# PowerSupply.net
KiCad netlist of a schematic drawn in Altium Designer
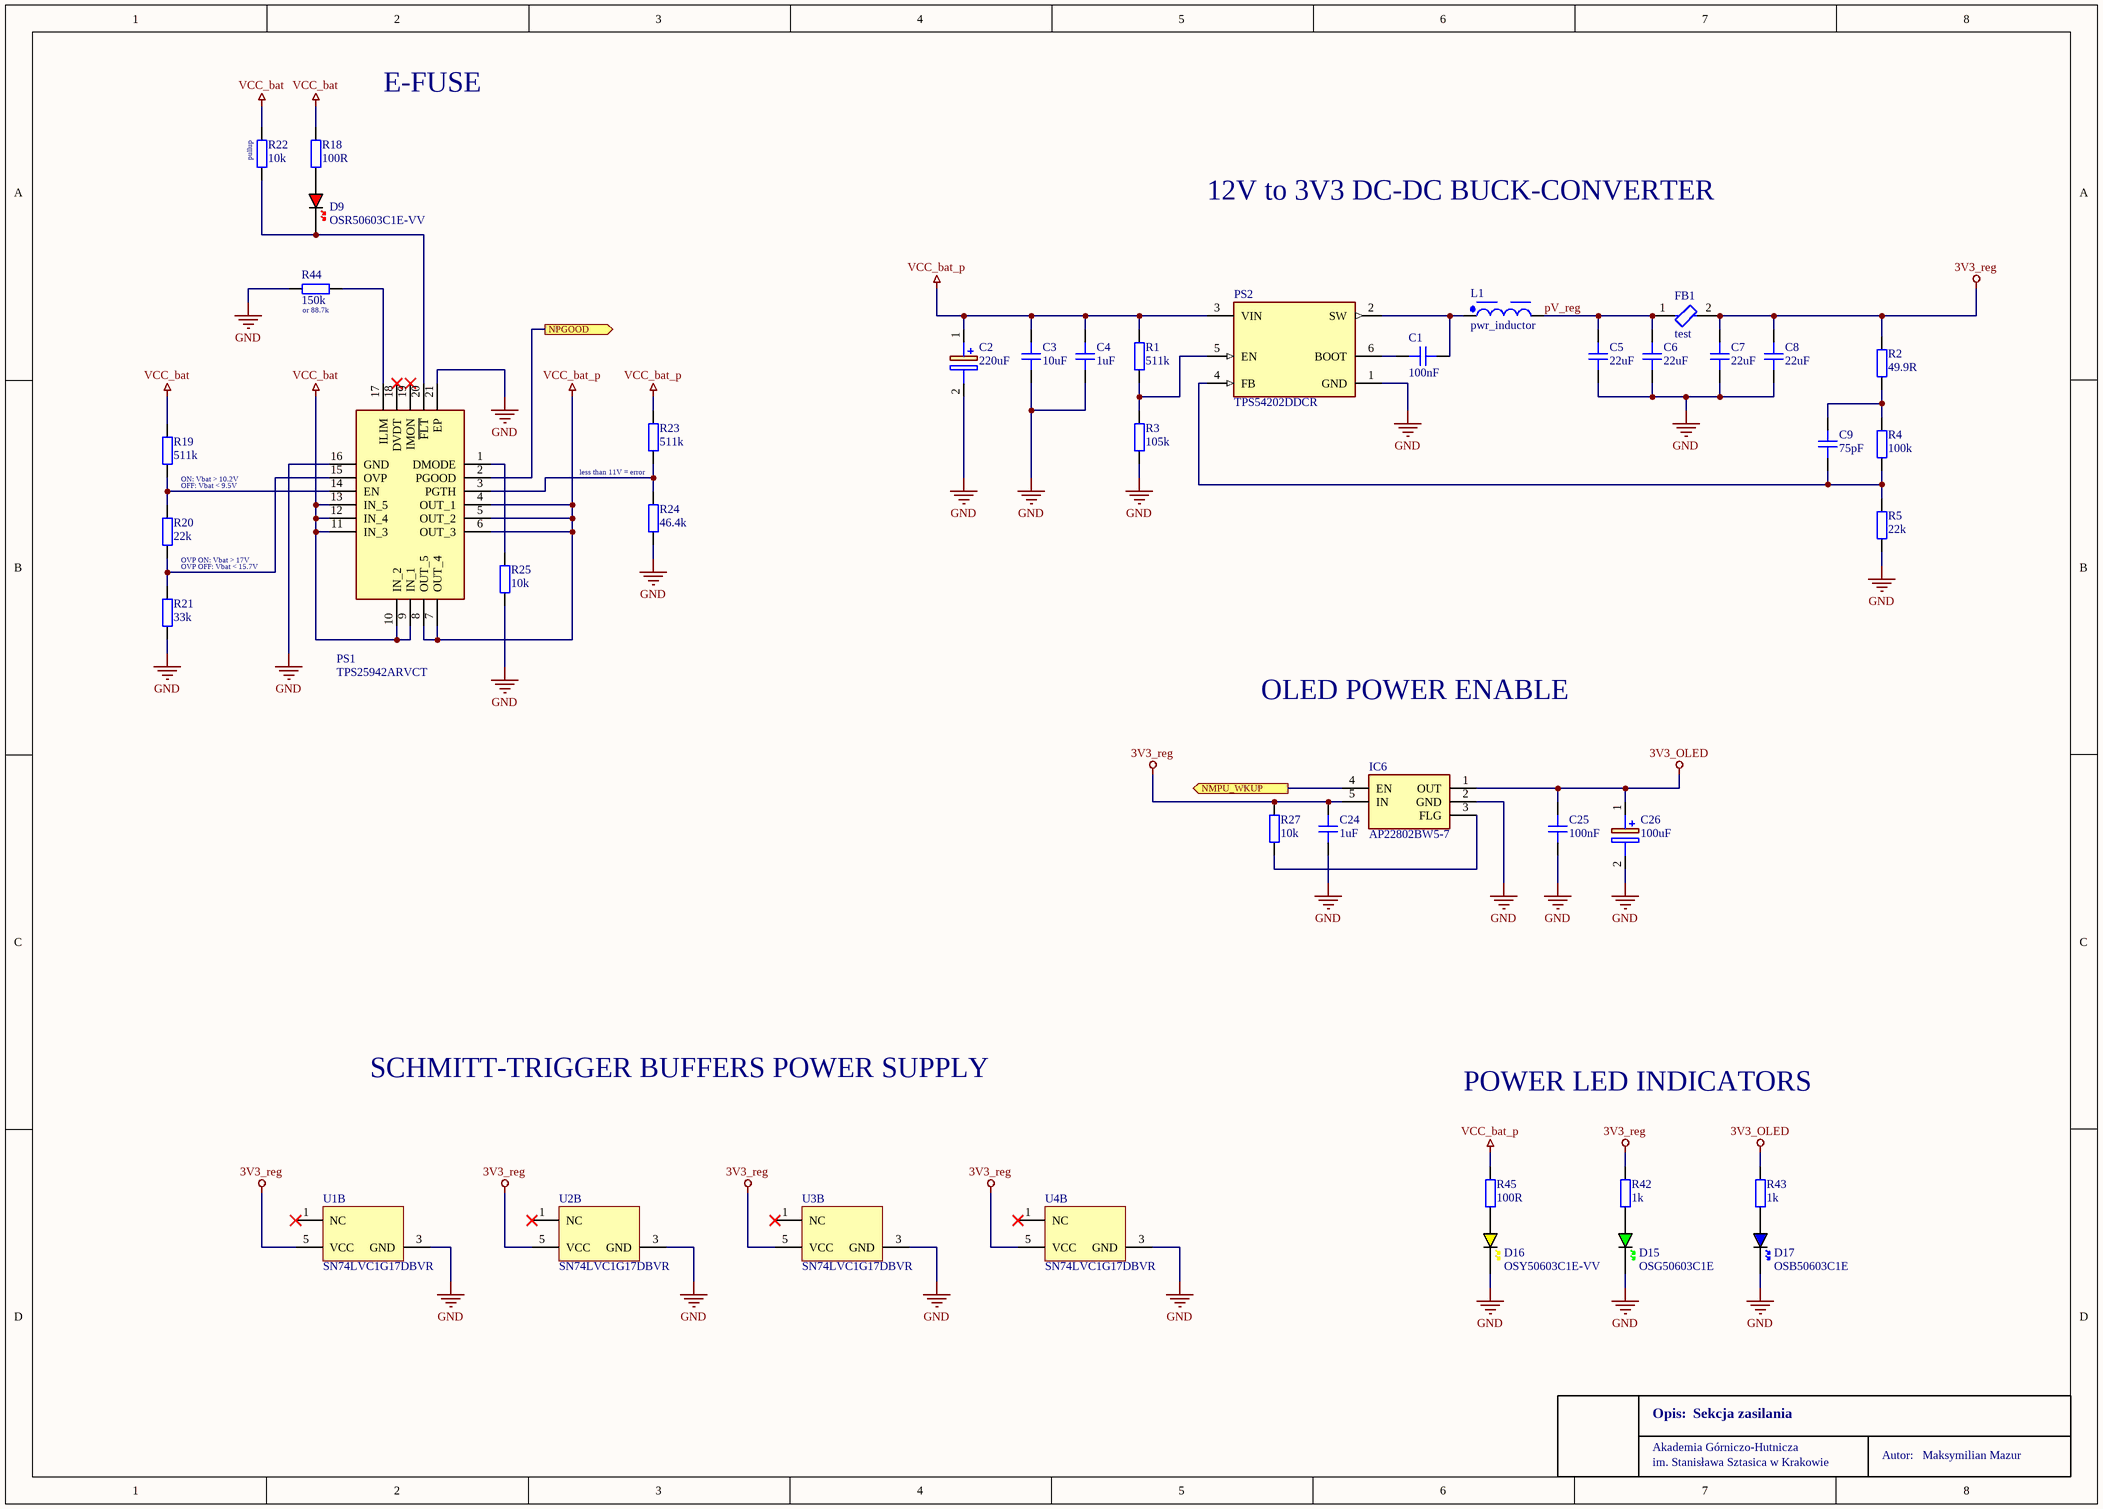
[diagram p0: PowerSupply.SchDoc]

(export (version "E")
  (design (tool "Eeschema 10.0.6"))
  (components
    (comp (ref "C1")
      (value "100nF")
      (footprint "CAP_0603")
      (description "Capacitor SMD 0603\r\nX7R\r\nLOW ESR")
      (libsource (lib "Schematic-Lib-PhilsLab") (part "CAP_0603"))
    )
    (comp (ref "C2")
      (value "220uF")
      (footprint "SamacSys:CAPAE660X810N")
      (description "Capacitor Polarised\r\n220uF 16V\r\n\r\nSC1C227M6L07KVR")
      (fields (field (name "MANUFACTURER_PART_NUMBER") "SC1C227M6L07KVR"))
      (libsource (lib "*") (part "SC1C227M6L07KVR"))
    )
    (comp (ref "C3")
      (value "10uF")
      (footprint "CAP_1206")
      (description "Capacitor SMD 1206\r\n25V")
      (libsource (lib "Schematic-Lib-PhilsLab") (part "CAP_1206"))
    )
    (comp (ref "C4")
      (value "1uF")
      (footprint "CAP_0603")
      (description "Capacitor SMD 0603\r\n25V")
      (libsource (lib "Schematic-Lib-PhilsLab") (part "CAP_0603"))
    )
    (comp (ref "C5")
      (value "22uF")
      (footprint "CAP_0603")
      (description "Capacitor SMD 0603\r\nX7R\r\nLOW ESR")
      (libsource (lib "Schematic-Lib-PhilsLab") (part "CAP_0603"))
    )
    (comp (ref "C6")
      (value "22uF")
      (footprint "CAP_0603")
      (description "Capacitor SMD 0603\r\nX7R\r\nLOW ESR")
      (libsource (lib "Schematic-Lib-PhilsLab") (part "CAP_0603"))
    )
    (comp (ref "C7")
      (value "22uF")
      (footprint "CAP_0603")
      (description "Capacitor SMD 0603\r\nX7R\r\nLOW ESR")
      (libsource (lib "Schematic-Lib-PhilsLab") (part "CAP_0603"))
    )
    (comp (ref "C8")
      (value "22uF")
      (footprint "CAP_0603")
      (description "Capacitor SMD 0603\r\nX7R\r\nLOW ESR")
      (libsource (lib "Schematic-Lib-PhilsLab") (part "CAP_0603"))
    )
    (comp (ref "C9")
      (value "75pF")
      (footprint "CAP_0603")
      (description "Capacitor SMD 0603")
      (libsource (lib "Schematic-Lib-PhilsLab") (part "CAP_0603"))
    )
    (comp (ref "C24")
      (value "1uF")
      (footprint "CAP_0603")
      (description "Capacitor SMD 0603")
      (libsource (lib "Schematic-Lib-PhilsLab") (part "CAP_0603"))
    )
    (comp (ref "C25")
      (value "100nF")
      (footprint "CAP_0603")
      (description "Capacitor SMD 0603")
      (libsource (lib "Schematic-Lib-PhilsLab") (part "CAP_0603"))
    )
    (comp (ref "C26")
      (value "100uF")
      (footprint "SamacSys:CAPPM3528X210N")
      (description "Kyocera AVX\r\nTAJB107M010RNJ")
      (fields
        (field (name "MANUFACTURER_PART_NUMBER") "TAJB107M010RNJ")
        (field (name "MOUSER PART NUMBER") "581-TAJB107M010R")
      )
      (libsource (lib "*") (part "TAJB107M010RNJ"))
    )
    (comp (ref "D9")
      (value "OSR50603C1E-VV")
      (footprint "LED_0603_RED")
      (description "LED 0603 RED SMD\r\nModel: OSR50603C1E")
      (libsource (lib "Schematic-Lib-PhilsLab") (part "LED_0603_RED"))
    )
    (comp (ref "D15")
      (value "OSG50603C1E")
      (footprint "LED_0603_GREEN")
      (description "LED 0603 GREEN SMD\r\nOSG50603C1E")
      (libsource (lib "Schematic-Lib-PhilsLab") (part "LED_0603_GREEN"))
    )
    (comp (ref "D16")
      (value "OSY50603C1E-VV")
      (footprint "LED_0603_YELLOW")
      (description "LED 0603 YELLOW SMD\r\nOSY50603C1E-VV")
      (libsource (lib "Schematic-Lib-PhilsLab") (part "LED_0603_YELLOW"))
    )
    (comp (ref "D17")
      (value "OSB50603C1E")
      (footprint "LED_0603_BLUE")
      (description "LED 0603 BLUE SMD")
      (libsource (lib "Schematic-Lib-PhilsLab") (part "LED_0603_BLUE"))
    )
    (comp (ref "FB1")
      (value "test")
      (footprint "FP-BLM18-0_15-t0_8-IPC_A")
      (description "Chip Ferrite Bead, 0603\r\n\r\nFor testing purpose")
      (fields (field (name "TOLERANCE") "25%"))
      (libsource (lib "Altium Content Vault") (part "5f30dd21d616792df468990f7003faa"))
    )
    (comp (ref "IC6")
      (value "AP22802BW5-7")
      (footprint "SamacSys:SOT95P285X140-5N")
      (description "Integrated Circuit")
      (fields (field (name "MOUSER PART NUMBER") "621-AP22802BW5-7"))
      (libsource (lib "*") (part "AP22802BW5-7"))
    )
    (comp (ref "L1")
      (value "pwr_inductor")
      (footprint "WE-PD_7345")
      (description "15uF, 2.7A  HPI0630-150")
      (fields (field (name "TOLERANCE") "20%"))
      (libsource (lib "Altium Content Vault") (part "Inductor - 2"))
    )
    (comp (ref "PS1")
      (value "TPS25942ARVCT")
      (footprint "SamacSys:QFN50P300X400X80-21N")
      (description "Power Supply")
      (fields (field (name "MOUSER PART NUMBER") "595-TPS25942ARVCT"))
      (libsource (lib "*") (part "TPS25942ARVCT"))
    )
    (comp (ref "PS2")
      (value "TPS54202DDCR")
      (footprint "FP-DDC0006A-IPC_B")
      (description "IC REG BUCK ADJ 2A TSOT23-6")
      (libsource (lib "Altium Content Vault") (part "35c2d3f1afc239a386b2ba50eead654"))
    )
    (comp (ref "R1")
      (value "511k")
      (footprint "RES_0603")
      (description "Resistor SMD 0603")
      (libsource (lib "Schematic-Lib-PhilsLab") (part "RES_0603"))
    )
    (comp (ref "R2")
      (value "49.9R")
      (footprint "RES_0603")
      (description "Resistor SMD 0603")
      (libsource (lib "Schematic-Lib-PhilsLab") (part "RES_0603"))
    )
    (comp (ref "R3")
      (value "105k")
      (footprint "RES_0603")
      (description "Resistor SMD 0603")
      (libsource (lib "Schematic-Lib-PhilsLab") (part "RES_0603"))
    )
    (comp (ref "R4")
      (value "100k")
      (footprint "RES_0603")
      (description "Resistor SMD 0603\r\nTolerance 1%")
      (libsource (lib "Schematic-Lib-PhilsLab") (part "RES_0603"))
    )
    (comp (ref "R5")
      (value "22k")
      (footprint "RES_0603")
      (description "Resistor SMD 0603\r\nTolerance 1%")
      (libsource (lib "Schematic-Lib-PhilsLab") (part "RES_0603"))
    )
    (comp (ref "R18")
      (value "100R")
      (footprint "RES_0603")
      (description "Resistor SMD 0603")
      (libsource (lib "Schematic-Lib-PhilsLab") (part "RES_0603"))
    )
    (comp (ref "R19")
      (value "511k")
      (footprint "RES_0603")
      (description "Resistor SMD 0603")
      (libsource (lib "Schematic-Lib-PhilsLab") (part "RES_0603"))
    )
    (comp (ref "R20")
      (value "22k")
      (footprint "RES_0603")
      (description "Resistor SMD 0603")
      (libsource (lib "Schematic-Lib-PhilsLab") (part "RES_0603"))
    )
    (comp (ref "R21")
      (value "33k")
      (footprint "RES_0603")
      (description "Resistor SMD 0603")
      (libsource (lib "Schematic-Lib-PhilsLab") (part "RES_0603"))
    )
    (comp (ref "R22")
      (value "10k")
      (footprint "RES_0603")
      (description "Resistor SMD 0603")
      (libsource (lib "Schematic-Lib-PhilsLab") (part "RES_0603"))
    )
    (comp (ref "R23")
      (value "511k")
      (footprint "RES_0603")
      (description "Resistor SMD 0603")
      (libsource (lib "Schematic-Lib-PhilsLab") (part "RES_0603"))
    )
    (comp (ref "R24")
      (value "46.4k")
      (footprint "RES_0603")
      (description "Resistor SMD 0603")
      (libsource (lib "Schematic-Lib-PhilsLab") (part "RES_0603"))
    )
    (comp (ref "R25")
      (value "10k")
      (footprint "RES_0603")
      (description "Resistor SMD 0603")
      (libsource (lib "Schematic-Lib-PhilsLab") (part "RES_0603"))
    )
    (comp (ref "R27")
      (value "10k")
      (footprint "RES_0603")
      (description "Resistor SMD 0603")
      (libsource (lib "Schematic-Lib-PhilsLab") (part "RES_0603"))
    )
    (comp (ref "R42")
      (value "1k")
      (footprint "RES_0603")
      (description "Resistor SMD 0603")
      (libsource (lib "Schematic-Lib-PhilsLab") (part "RES_0603"))
    )
    (comp (ref "R43")
      (value "1k")
      (footprint "RES_0603")
      (description "Resistor SMD 0603")
      (libsource (lib "Schematic-Lib-PhilsLab") (part "RES_0603"))
    )
    (comp (ref "R44")
      (value "150k")
      (footprint "RES_0603")
      (description "Resistor SMD 0603")
      (libsource (lib "Schematic-Lib-PhilsLab") (part "RES_0603"))
    )
    (comp (ref "R45")
      (value "100R")
      (footprint "RES_0603")
      (description "Resistor SMD 0603")
      (libsource (lib "Schematic-Lib-PhilsLab") (part "RES_0603"))
    )
    (comp (ref "U1")
      (value "SN74LVC1G17DBVR")
      (footprint "DBV0005A_L")
      (description "Single Schmitt-Trigger Buffer, DBV0005A, LARGE T&R")
      (fields
        (field (name "MANUFACTURER") "Texas Instruments")
        (field (name "GENERIC PART NUMBER") "SN74LVC1G17")
      )
      (libsource (lib "Altium Content Vault") (part "TI-SN74XXX1XXX-XX-5-SCHMITT"))
    )
    (comp (ref "U2")
      (value "SN74LVC1G17DBVR")
      (footprint "DBV0005A_L")
      (description "Single Schmitt-Trigger Buffer, DBV0005A, LARGE T&R")
      (fields
        (field (name "MANUFACTURER") "Texas Instruments")
        (field (name "GENERIC PART NUMBER") "SN74LVC1G17")
      )
      (libsource (lib "Altium Content Vault") (part "TI-SN74XXX1XXX-XX-5-SCHMITT"))
    )
    (comp (ref "U3")
      (value "SN74LVC1G17DBVR")
      (footprint "DBV0005A_L")
      (description "Single Schmitt-Trigger Buffer, DBV0005A, LARGE T&R")
      (fields
        (field (name "MANUFACTURER") "Texas Instruments")
        (field (name "GENERIC PART NUMBER") "SN74LVC1G17")
      )
      (libsource (lib "Altium Content Vault") (part "TI-SN74XXX1XXX-XX-5-SCHMITT"))
    )
    (comp (ref "U4")
      (value "SN74LVC1G17DBVR")
      (footprint "DBV0005A_L")
      (description "Single Schmitt-Trigger Buffer, DBV0005A, LARGE T&R")
      (fields
        (field (name "MANUFACTURER") "Texas Instruments")
        (field (name "GENERIC PART NUMBER") "SN74LVC1G17")
      )
      (libsource (lib "Altium Content Vault") (part "TI-SN74XXX1XXX-XX-5-SCHMITT"))
    )
  )
  (nets
    (net (code "1") (name "/NMPU_WKUP") (class "Default")
      (node (ref "IC6") (pin "4") (pinfunction "EN_4") (pintype "passive"))
    )
    (net (code "2") (name "/NPGOOD") (class "Default")
      (node (ref "PS1") (pin "2") (pinfunction "PGOOD_2") (pintype "passive"))
    )
    (net (code "3") (name "/pV_reg") (class "Default")
      (node (ref "C5") (pin "2") (pinfunction "2_2") (pintype "passive"))
      (node (ref "C6") (pin "2") (pinfunction "2_2") (pintype "passive"))
      (node (ref "FB1") (pin "1") (pinfunction "1_1") (pintype "passive"))
      (node (ref "L1") (pin "2") (pinfunction "2_2") (pintype "passive"))
    )
    (net (code "4") (name "3V3_OLED") (class "Default")
      (node (ref "C25") (pin "2") (pinfunction "2_2") (pintype "passive"))
      (node (ref "C26") (pin "1") (pinfunction "+_1") (pintype "passive"))
      (node (ref "IC6") (pin "1") (pinfunction "OUT_1") (pintype "passive"))
      (node (ref "R43") (pin "2") (pinfunction "2_2") (pintype "passive"))
    )
    (net (code "5") (name "3V3_reg") (class "Default")
      (node (ref "C24") (pin "2") (pinfunction "2_2") (pintype "passive"))
      (node (ref "C7") (pin "2") (pinfunction "2_2") (pintype "passive"))
      (node (ref "C8") (pin "2") (pinfunction "2_2") (pintype "passive"))
      (node (ref "FB1") (pin "2") (pinfunction "2_2") (pintype "passive"))
      (node (ref "IC6") (pin "5") (pinfunction "IN_5") (pintype "passive"))
      (node (ref "R2") (pin "2") (pinfunction "2_2") (pintype "passive"))
      (node (ref "R27") (pin "2") (pinfunction "2_2") (pintype "passive"))
      (node (ref "R42") (pin "2") (pinfunction "2_2") (pintype "passive"))
      (node (ref "U1") (pin "5") (pinfunction "VCC_5") (pintype "power_in"))
      (node (ref "U2") (pin "5") (pinfunction "VCC_5") (pintype "power_in"))
      (node (ref "U3") (pin "5") (pinfunction "VCC_5") (pintype "power_in"))
      (node (ref "U4") (pin "5") (pinfunction "VCC_5") (pintype "power_in"))
    )
    (net (code "6") (name "GND") (class "Default")
      (node (ref "C2") (pin "2") (pinfunction "-_2") (pintype "passive"))
      (node (ref "C24") (pin "1") (pinfunction "1_1") (pintype "passive"))
      (node (ref "C25") (pin "1") (pinfunction "1_1") (pintype "passive"))
      (node (ref "C26") (pin "2") (pinfunction "-_2") (pintype "passive"))
      (node (ref "C3") (pin "1") (pinfunction "1_1") (pintype "passive"))
      (node (ref "C4") (pin "1") (pinfunction "1_1") (pintype "passive"))
      (node (ref "C5") (pin "1") (pinfunction "1_1") (pintype "passive"))
      (node (ref "C6") (pin "1") (pinfunction "1_1") (pintype "passive"))
      (node (ref "C7") (pin "1") (pinfunction "1_1") (pintype "passive"))
      (node (ref "C8") (pin "1") (pinfunction "1_1") (pintype "passive"))
      (node (ref "D15") (pin "K") (pinfunction "K_K") (pintype "passive"))
      (node (ref "D16") (pin "K") (pinfunction "K_K") (pintype "passive"))
      (node (ref "D17") (pin "K") (pinfunction "K_K") (pintype "passive"))
      (node (ref "IC6") (pin "2") (pinfunction "GND_2") (pintype "passive"))
      (node (ref "PS1") (pin "16") (pinfunction "GND_16") (pintype "passive"))
      (node (ref "PS1") (pin "21") (pinfunction "EP_21") (pintype "passive"))
      (node (ref "PS2") (pin "1") (pinfunction "GND_1") (pintype "power_in"))
      (node (ref "R21") (pin "1") (pinfunction "1_1") (pintype "passive"))
      (node (ref "R24") (pin "1") (pinfunction "1_1") (pintype "passive"))
      (node (ref "R25") (pin "1") (pinfunction "1_1") (pintype "passive"))
      (node (ref "R3") (pin "1") (pinfunction "1_1") (pintype "passive"))
      (node (ref "R44") (pin "2") (pinfunction "2_2") (pintype "passive"))
      (node (ref "R5") (pin "2") (pinfunction "2_2") (pintype "passive"))
      (node (ref "U1") (pin "3") (pinfunction "GND_3") (pintype "power_in"))
      (node (ref "U2") (pin "3") (pinfunction "GND_3") (pintype "power_in"))
      (node (ref "U3") (pin "3") (pinfunction "GND_3") (pintype "power_in"))
      (node (ref "U4") (pin "3") (pinfunction "GND_3") (pintype "power_in"))
    )
    (net (code "7") (name "Net-(C9-Pad2)") (class "Default")
      (node (ref "C9") (pin "2") (pinfunction "2_2") (pintype "passive"))
      (node (ref "R2") (pin "1") (pinfunction "1_1") (pintype "passive"))
      (node (ref "R4") (pin "2") (pinfunction "2_2") (pintype "passive"))
    )
    (net (code "8") (name "Net-(D9-PadA)") (class "Default")
      (node (ref "D9") (pin "A") (pinfunction "A_A") (pintype "passive"))
      (node (ref "R18") (pin "1") (pinfunction "1_1") (pintype "passive"))
    )
    (net (code "9") (name "Net-(D15-PadA)") (class "Default")
      (node (ref "D15") (pin "A") (pinfunction "A_A") (pintype "passive"))
      (node (ref "R42") (pin "1") (pinfunction "1_1") (pintype "passive"))
    )
    (net (code "10") (name "Net-(D16-PadA)") (class "Default")
      (node (ref "D16") (pin "A") (pinfunction "A_A") (pintype "passive"))
      (node (ref "R45") (pin "1") (pinfunction "1_1") (pintype "passive"))
    )
    (net (code "11") (name "Net-(D17-PadA)") (class "Default")
      (node (ref "D17") (pin "A") (pinfunction "A_A") (pintype "passive"))
      (node (ref "R43") (pin "1") (pinfunction "1_1") (pintype "passive"))
    )
    (net (code "12") (name "Net-(IC6-FLG)") (class "Default")
      (node (ref "IC6") (pin "3") (pinfunction "FLG_3") (pintype "passive"))
      (node (ref "R27") (pin "1") (pinfunction "1_1") (pintype "passive"))
    )
    (net (code "13") (name "Net-(PS1-DMODE)") (class "Default")
      (node (ref "PS1") (pin "1") (pinfunction "DMODE_1") (pintype "passive"))
      (node (ref "R25") (pin "2") (pinfunction "2_2") (pintype "passive"))
    )
    (net (code "14") (name "Net-(PS1-EN)") (class "Default")
      (node (ref "PS1") (pin "14") (pinfunction "EN_14") (pintype "passive"))
      (node (ref "R19") (pin "1") (pinfunction "1_1") (pintype "passive"))
      (node (ref "R20") (pin "2") (pinfunction "2_2") (pintype "passive"))
    )
    (net (code "15") (name "Net-(PS1-ILIM)") (class "Default")
      (node (ref "PS1") (pin "17") (pinfunction "ILIM_17") (pintype "passive"))
      (node (ref "R44") (pin "1") (pinfunction "1_1") (pintype "passive"))
    )
    (net (code "16") (name "Net-(PS1-OVP)") (class "Default")
      (node (ref "PS1") (pin "15") (pinfunction "OVP_15") (pintype "passive"))
      (node (ref "R20") (pin "1") (pinfunction "1_1") (pintype "passive"))
      (node (ref "R21") (pin "2") (pinfunction "2_2") (pintype "passive"))
    )
    (net (code "17") (name "Net-(PS1-PGTH)") (class "Default")
      (node (ref "PS1") (pin "3") (pinfunction "PGTH_3") (pintype "passive"))
      (node (ref "R23") (pin "1") (pinfunction "1_1") (pintype "passive"))
      (node (ref "R24") (pin "2") (pinfunction "2_2") (pintype "passive"))
    )
    (net (code "18") (name "Net-(PS1-~{FLT})") (class "Default")
      (node (ref "D9") (pin "K") (pinfunction "K_K") (pintype "passive"))
      (node (ref "PS1") (pin "20") (pinfunction "~{FLT}_20") (pintype "passive"))
      (node (ref "R22") (pin "1") (pinfunction "1_1") (pintype "passive"))
    )
    (net (code "19") (name "Net-(PS2-BOOT)") (class "Default")
      (node (ref "C1") (pin "2") (pinfunction "2_2") (pintype "passive"))
      (node (ref "PS2") (pin "6") (pinfunction "BOOT_6") (pintype "passive"))
    )
    (net (code "20") (name "Net-(PS2-EN)") (class "Default")
      (node (ref "PS2") (pin "5") (pinfunction "EN_5") (pintype "input"))
      (node (ref "R1") (pin "1") (pinfunction "1_1") (pintype "passive"))
      (node (ref "R3") (pin "2") (pinfunction "2_2") (pintype "passive"))
    )
    (net (code "21") (name "Net-(PS2-FB)") (class "Default")
      (node (ref "C9") (pin "1") (pinfunction "1_1") (pintype "passive"))
      (node (ref "PS2") (pin "4") (pinfunction "FB_4") (pintype "input"))
      (node (ref "R4") (pin "1") (pinfunction "1_1") (pintype "passive"))
      (node (ref "R5") (pin "1") (pinfunction "1_1") (pintype "passive"))
    )
    (net (code "22") (name "Net-(PS2-SW)") (class "Default")
      (node (ref "C1") (pin "1") (pinfunction "1_1") (pintype "passive"))
      (node (ref "L1") (pin "1") (pinfunction "1_1") (pintype "passive"))
      (node (ref "PS2") (pin "2") (pinfunction "SW_2") (pintype "output"))
    )
    (net (code "23") (name "VCC_bat") (class "Default")
      (node (ref "PS1") (pin "10") (pinfunction "IN_2_10") (pintype "passive"))
      (node (ref "PS1") (pin "11") (pinfunction "IN_3_11") (pintype "passive"))
      (node (ref "PS1") (pin "12") (pinfunction "IN_4_12") (pintype "passive"))
      (node (ref "PS1") (pin "13") (pinfunction "IN_5_13") (pintype "passive"))
      (node (ref "PS1") (pin "9") (pinfunction "IN_1_9") (pintype "passive"))
      (node (ref "R18") (pin "2") (pinfunction "2_2") (pintype "passive"))
      (node (ref "R19") (pin "2") (pinfunction "2_2") (pintype "passive"))
      (node (ref "R22") (pin "2") (pinfunction "2_2") (pintype "passive"))
    )
    (net (code "24") (name "VCC_bat_p") (class "Default")
      (node (ref "C2") (pin "1") (pinfunction "+_1") (pintype "passive"))
      (node (ref "C3") (pin "2") (pinfunction "2_2") (pintype "passive"))
      (node (ref "C4") (pin "2") (pinfunction "2_2") (pintype "passive"))
      (node (ref "PS1") (pin "4") (pinfunction "OUT_1_4") (pintype "passive"))
      (node (ref "PS1") (pin "5") (pinfunction "OUT_2_5") (pintype "passive"))
      (node (ref "PS1") (pin "6") (pinfunction "OUT_3_6") (pintype "passive"))
      (node (ref "PS1") (pin "7") (pinfunction "OUT_4_7") (pintype "passive"))
      (node (ref "PS1") (pin "8") (pinfunction "OUT_5_8") (pintype "passive"))
      (node (ref "PS2") (pin "3") (pinfunction "VIN_3") (pintype "power_in"))
      (node (ref "R1") (pin "2") (pinfunction "2_2") (pintype "passive"))
      (node (ref "R23") (pin "2") (pinfunction "2_2") (pintype "passive"))
      (node (ref "R45") (pin "2") (pinfunction "2_2") (pintype "passive"))
    )
    (net (code "25") (name "unconnected-(PS1-DVDT-Pad18)") (class "Default")
      (node (ref "PS1") (pin "18") (pinfunction "DVDT_18") (pintype "passive+no_connect"))
    )
    (net (code "26") (name "unconnected-(PS1-IMON-Pad19)") (class "Default")
      (node (ref "PS1") (pin "19") (pinfunction "IMON_19") (pintype "passive+no_connect"))
    )
    (net (code "27") (name "unconnected-(U1B-NC-Pad1)") (class "Default")
      (node (ref "U1") (pin "1") (pinfunction "NC_1") (pintype "passive+no_connect"))
    )
    (net (code "28") (name "unconnected-(U2B-NC-Pad1)") (class "Default")
      (node (ref "U2") (pin "1") (pinfunction "NC_1") (pintype "passive+no_connect"))
    )
    (net (code "29") (name "unconnected-(U3B-NC-Pad1)") (class "Default")
      (node (ref "U3") (pin "1") (pinfunction "NC_1") (pintype "passive+no_connect"))
    )
    (net (code "30") (name "unconnected-(U4B-NC-Pad1)") (class "Default")
      (node (ref "U4") (pin "1") (pinfunction "NC_1") (pintype "passive+no_connect"))
    )
  )
)
